# PWR_5V_3A.net
KiCad netlist of a schematic drawn in Altium Designer
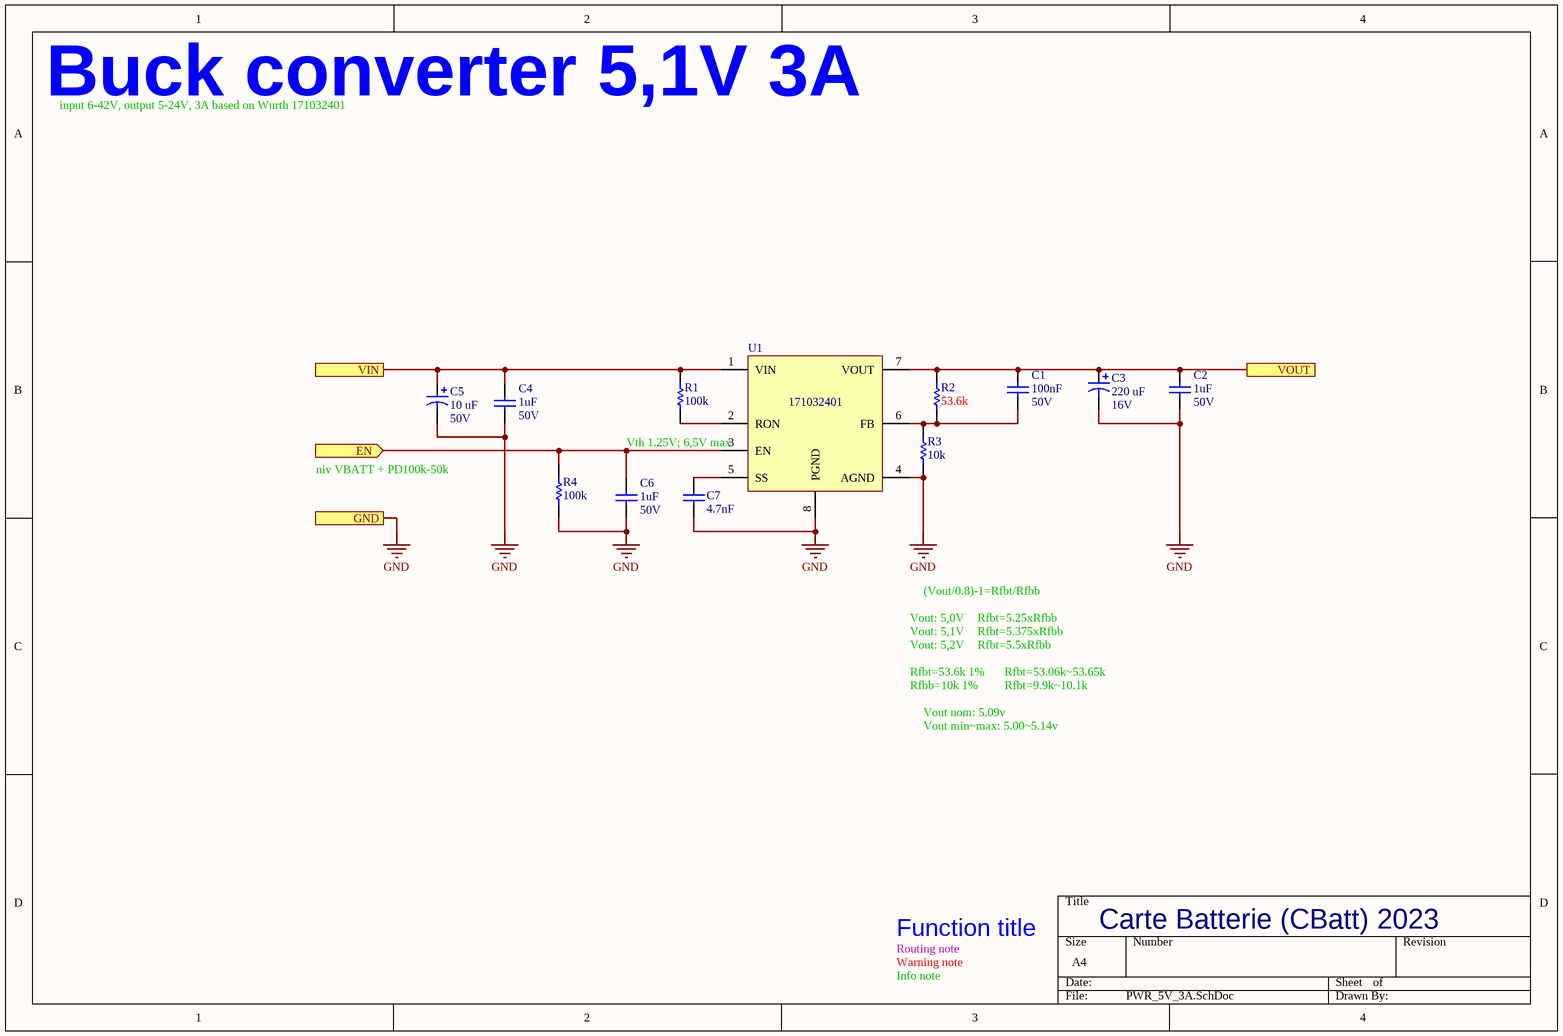
[diagram p0: PWR_5V_3A.SchDoc]

(export (version "E")
  (design (tool "Eeschema 10.0.6"))
  (components
    (comp (ref "C1")
      (value "100nF")
      (footprint "WCAP-CSGP_0603, 1.6x0.8x0.8")
      (description "CAP CER 100nF 50V X7R 0603")
      (fields
        (field (name "RATEDVOLTAGE") "50V")
        (field (name "MANUFACTURER") "Wurth Elektronik")
        (field (name "MANUFACTURER PART NUMBER") "885012206095")
      )
      (libsource (lib "Condensateur") (part "WCAP-CSGP, 885012206095"))
    )
    (comp (ref "C2")
      (value "1uF")
      (footprint "WCAP-CSGP_0805, 2x1.25x1.25")
      (description "CAP CER 1uF 50V X7R 0805")
      (fields
        (field (name "MANUFACTURER") "Wurth Elektronik")
        (field (name "MANUFACTURER PART NUMBER") "885012207103")
        (field (name "RATEDVOLTAGE") "50V")
      )
      (libsource (lib "Condensateur") (part "WCAP-CSGP, 885012207103"))
    )
    (comp (ref "C3")
      (value "220 uF")
      (footprint "WCAP-ATG8_6.3x11x2.5x0.5")
      (description "CAP Alu 220 UF 20% 16 V")
      (fields
        (field (name "MANUFACTURER") "Wurth Elektronik")
        (field (name "MANUFACTURER PART NUMBER") "860010373010")
        (field (name "RATEDVOLTAGE") "16V")
      )
      (libsource (lib "Condensateur") (part "WCAP-ATG8, 860010373010"))
    )
    (comp (ref "C4")
      (value "1uF")
      (footprint "WCAP-CSGP_0805, 2x1.25x1.25")
      (description "CAP CER 1uF 50V X7R 0805")
      (fields
        (field (name "MANUFACTURER") "Wurth Elektronik")
        (field (name "MANUFACTURER PART NUMBER") "885012207103")
        (field (name "RATEDVOLTAGE") "50V")
      )
      (libsource (lib "Condensateur") (part "WCAP-CSGP, 885012207103"))
    )
    (comp (ref "C5")
      (value "10 uF")
      (footprint "WCAP-ATG8_5x11x2x0.5")
      (description "CAP Alu 10 UF 20% 50 V")
      (fields
        (field (name "MANUFACTURER") "Wurth Elektronik")
        (field (name "MANUFACTURER PART NUMBER") "860010672009")
        (field (name "RATEDVOLTAGE") "50V")
      )
      (libsource (lib "Condensateur") (part "WCAP-ATG8, 860010672009"))
    )
    (comp (ref "C6")
      (value "1uF")
      (footprint "WCAP-CSGP_0805, 2x1.25x1.25")
      (description "CAP CER 1uF 50V X7R 0805")
      (fields
        (field (name "MANUFACTURER") "Wurth Elektronik")
        (field (name "MANUFACTURER PART NUMBER") "885012207103")
        (field (name "RATEDVOLTAGE") "50V")
      )
      (libsource (lib "Condensateur") (part "WCAP-CSGP, 885012207103"))
    )
    (comp (ref "C7")
      (value "4.7nF")
      (footprint "WCAP-CSGP_0603, 1.6x0.8x0.8")
      (description "CAP CER 4.7nF 50V X7R 0603")
      (fields
        (field (name "MANUFACTURER") "Wurth Elektronik")
        (field (name "MANUFACTURER PART NUMBER") "885012206087")
      )
      (libsource (lib "Condensateur") (part "WCAP-CSGP, 885012206087"))
    )
    (comp (ref "R1")
      (value "100k")
      (footprint "RESC1608X06N")
      (description "RES SMD 100K OHM 1% 1/10W 0603")
      (fields
        (field (name "MANUFACTURER") "Yageo")
        (field (name "MANUFACTURER PART NUMBER") "RC0603FR-07100KL")
      )
      (libsource (lib "Resistance") (part "RC0603FR-07100KL"))
    )
    (comp (ref "R2")
      (value "53.6k")
      (footprint "RESC1608X06N")
      (description "RES SMD 10K OHM 1% 1/10W 0603")
      (fields
        (field (name "MANUFACTURER") "Yageo")
        (field (name "MANUFACTURER PART NUMBER") "RC0603FR-0710KL")
      )
      (libsource (lib "Resistance") (part "RC0603FR-0710KL"))
    )
    (comp (ref "R3")
      (value "10k")
      (footprint "RESC1608X06N")
      (description "RES SMD 10K OHM 1% 1/10W 0603")
      (fields
        (field (name "MANUFACTURER") "Yageo")
        (field (name "MANUFACTURER PART NUMBER") "RC0603FR-0710KL")
      )
      (libsource (lib "Resistance") (part "RC0603FR-0710KL"))
    )
    (comp (ref "R4")
      (value "100k")
      (footprint "RESC1608X06N")
      (description "RES SMD 100K OHM 1% 1/10W 0603")
      (fields
        (field (name "MANUFACTURER") "Yageo")
        (field (name "MANUFACTURER PART NUMBER") "RC0603FR-07100KL")
      )
      (libsource (lib "Resistance") (part "RC0603FR-07100KL"))
    )
    (comp (ref "U1")
      (value "171032401")
      (footprint "WPME-VDRM_TO263-7EP")
      (description "WPME-VDRM DCDC 6-42Vin, 5-24Vout, 3Aout TO263-7EP")
      (fields (field (name "MANUFACTURER") "Wurth Elektronik"))
      (libsource (lib "Alimentation") (part "171032401"))
    )
  )
  (nets
    (net (code "1") (name "/EN") (class "Default")
      (node (ref "C6") (pin "2") (pinfunction "2_2") (pintype "passive"))
      (node (ref "R4") (pin "2") (pinfunction "2_2") (pintype "passive"))
      (node (ref "U1") (pin "3") (pinfunction "EN_3") (pintype "passive"))
    )
    (net (code "2") (name "/VIN") (class "Default")
      (node (ref "C4") (pin "2") (pinfunction "2_2") (pintype "passive"))
      (node (ref "C5") (pin "1") (pinfunction "1_1") (pintype "passive"))
      (node (ref "R1") (pin "2") (pinfunction "2_2") (pintype "passive"))
      (node (ref "U1") (pin "1") (pinfunction "VIN_1") (pintype "passive"))
    )
    (net (code "3") (name "/VOUT") (class "Default")
      (node (ref "C1") (pin "2") (pinfunction "2_2") (pintype "passive"))
      (node (ref "C2") (pin "2") (pinfunction "2_2") (pintype "passive"))
      (node (ref "C3") (pin "1") (pinfunction "1_1") (pintype "passive"))
      (node (ref "R2") (pin "2") (pinfunction "2_2") (pintype "passive"))
      (node (ref "U1") (pin "7") (pinfunction "VOUT_7") (pintype "passive"))
    )
    (net (code "4") (name "GND") (class "Default")
      (node (ref "C2") (pin "1") (pinfunction "1_1") (pintype "passive"))
      (node (ref "C3") (pin "2") (pinfunction "2_2") (pintype "passive"))
      (node (ref "C4") (pin "1") (pinfunction "1_1") (pintype "passive"))
      (node (ref "C5") (pin "2") (pinfunction "2_2") (pintype "passive"))
      (node (ref "C6") (pin "1") (pinfunction "1_1") (pintype "passive"))
      (node (ref "C7") (pin "1") (pinfunction "1_1") (pintype "passive"))
      (node (ref "R3") (pin "1") (pinfunction "1_1") (pintype "passive"))
      (node (ref "R4") (pin "1") (pinfunction "1_1") (pintype "passive"))
      (node (ref "U1") (pin "4") (pinfunction "AGND_4") (pintype "passive"))
      (node (ref "U1") (pin "8") (pinfunction "PGND_8") (pintype "passive"))
    )
    (net (code "5") (name "Net-(U1-FB)") (class "Default")
      (node (ref "C1") (pin "1") (pinfunction "1_1") (pintype "passive"))
      (node (ref "R2") (pin "1") (pinfunction "1_1") (pintype "passive"))
      (node (ref "R3") (pin "2") (pinfunction "2_2") (pintype "passive"))
      (node (ref "U1") (pin "6") (pinfunction "FB_6") (pintype "passive"))
    )
    (net (code "6") (name "Net-(U1-RON)") (class "Default")
      (node (ref "R1") (pin "1") (pinfunction "1_1") (pintype "passive"))
      (node (ref "U1") (pin "2") (pinfunction "RON_2") (pintype "passive"))
    )
    (net (code "7") (name "Net-(U1-SS)") (class "Default")
      (node (ref "C7") (pin "2") (pinfunction "2_2") (pintype "passive"))
      (node (ref "U1") (pin "5") (pinfunction "SS_5") (pintype "passive"))
    )
  )
)
